# miniDCU_main.net
KiCad netlist of a schematic drawn in EAGLE
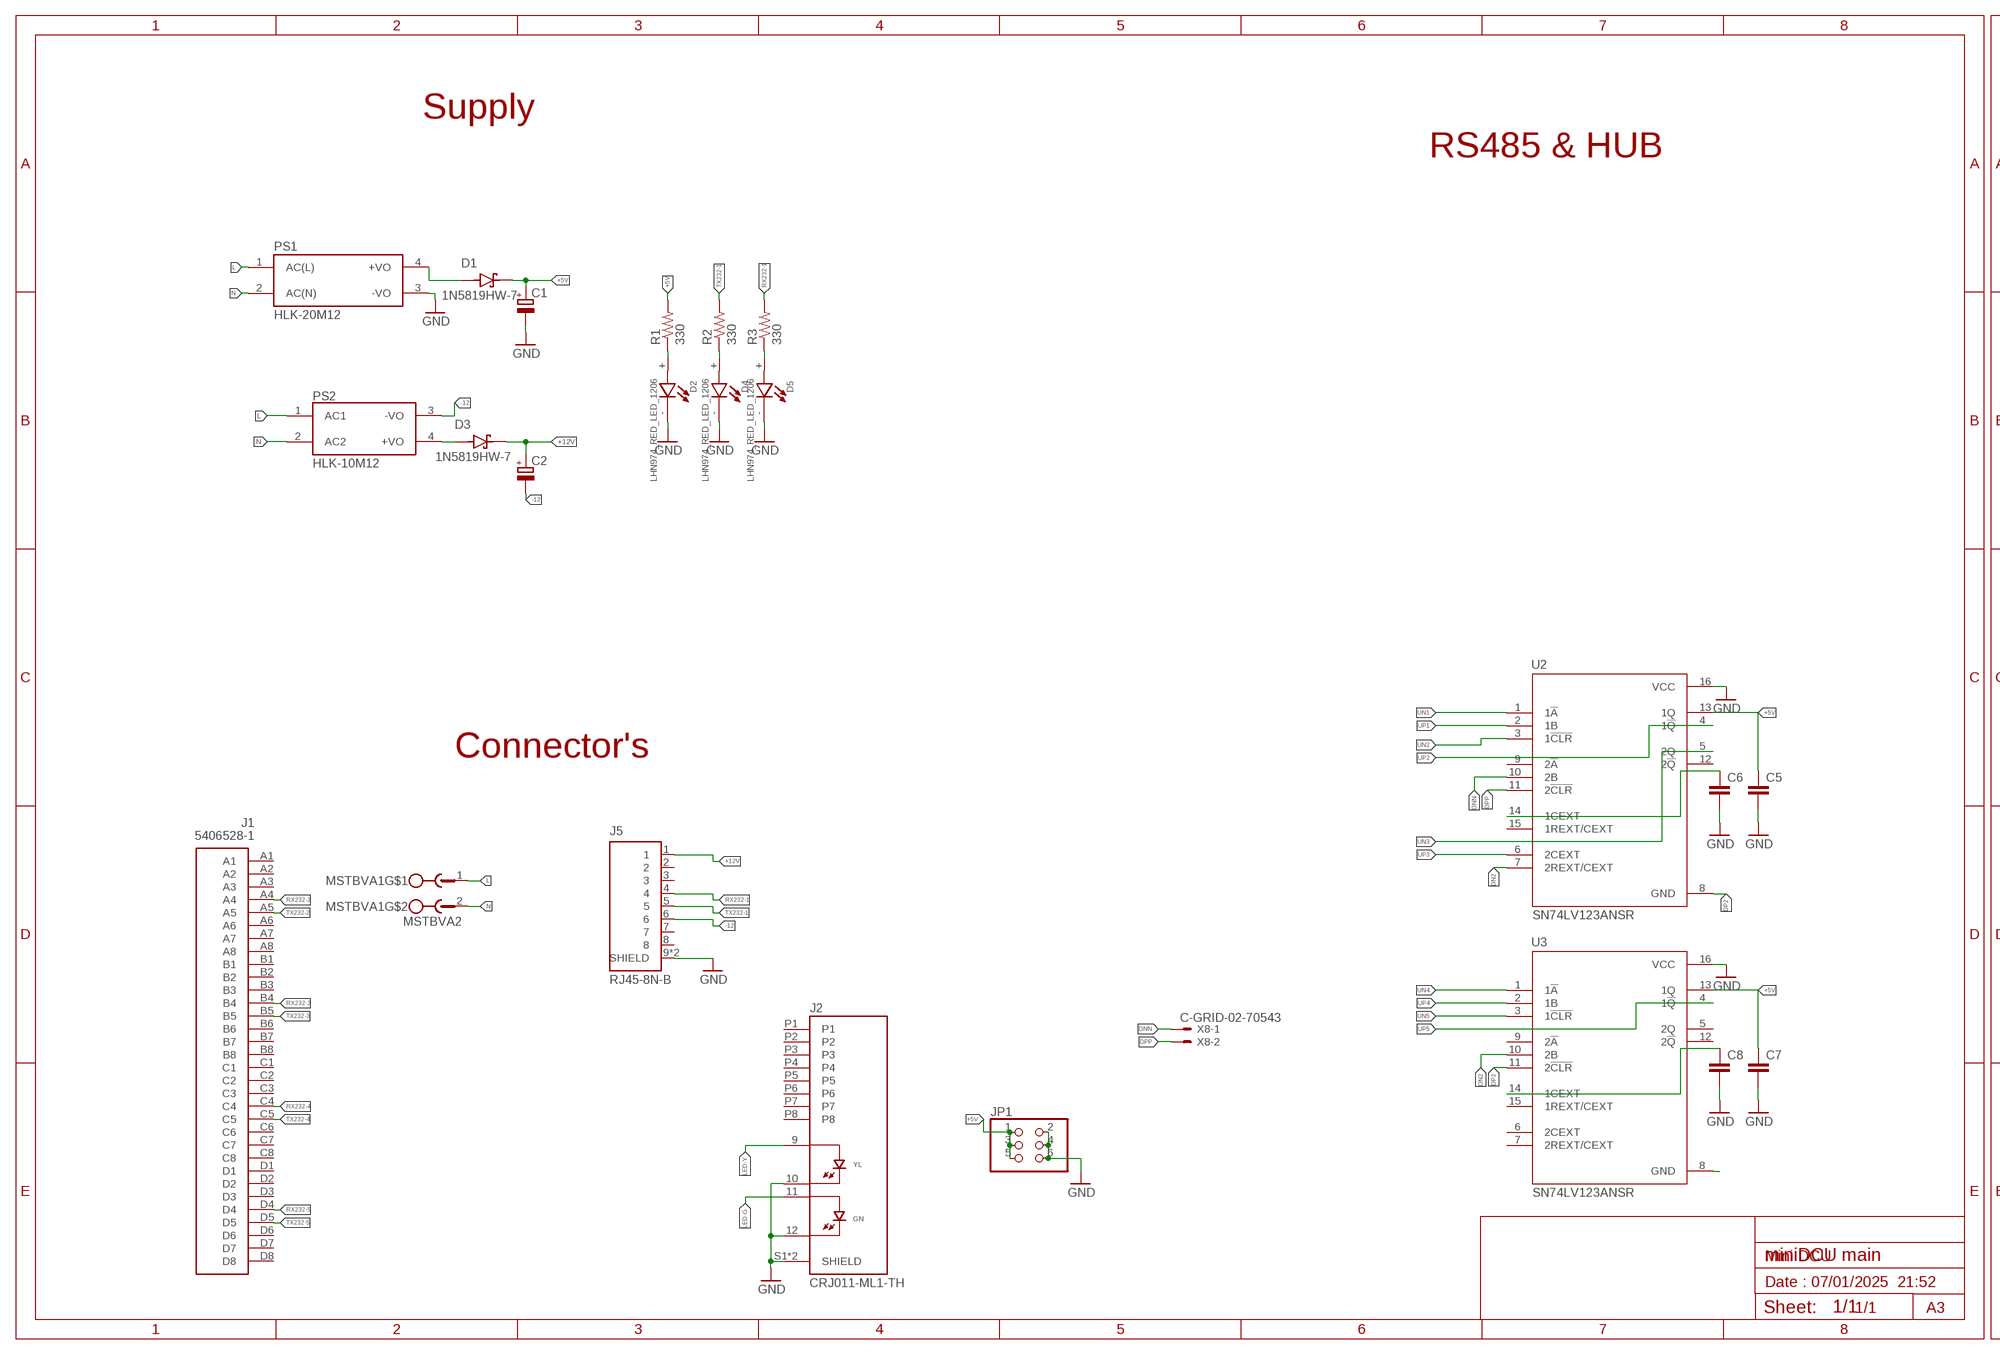
[diagram p0: schematic, sheet 1, part 1 of 2]
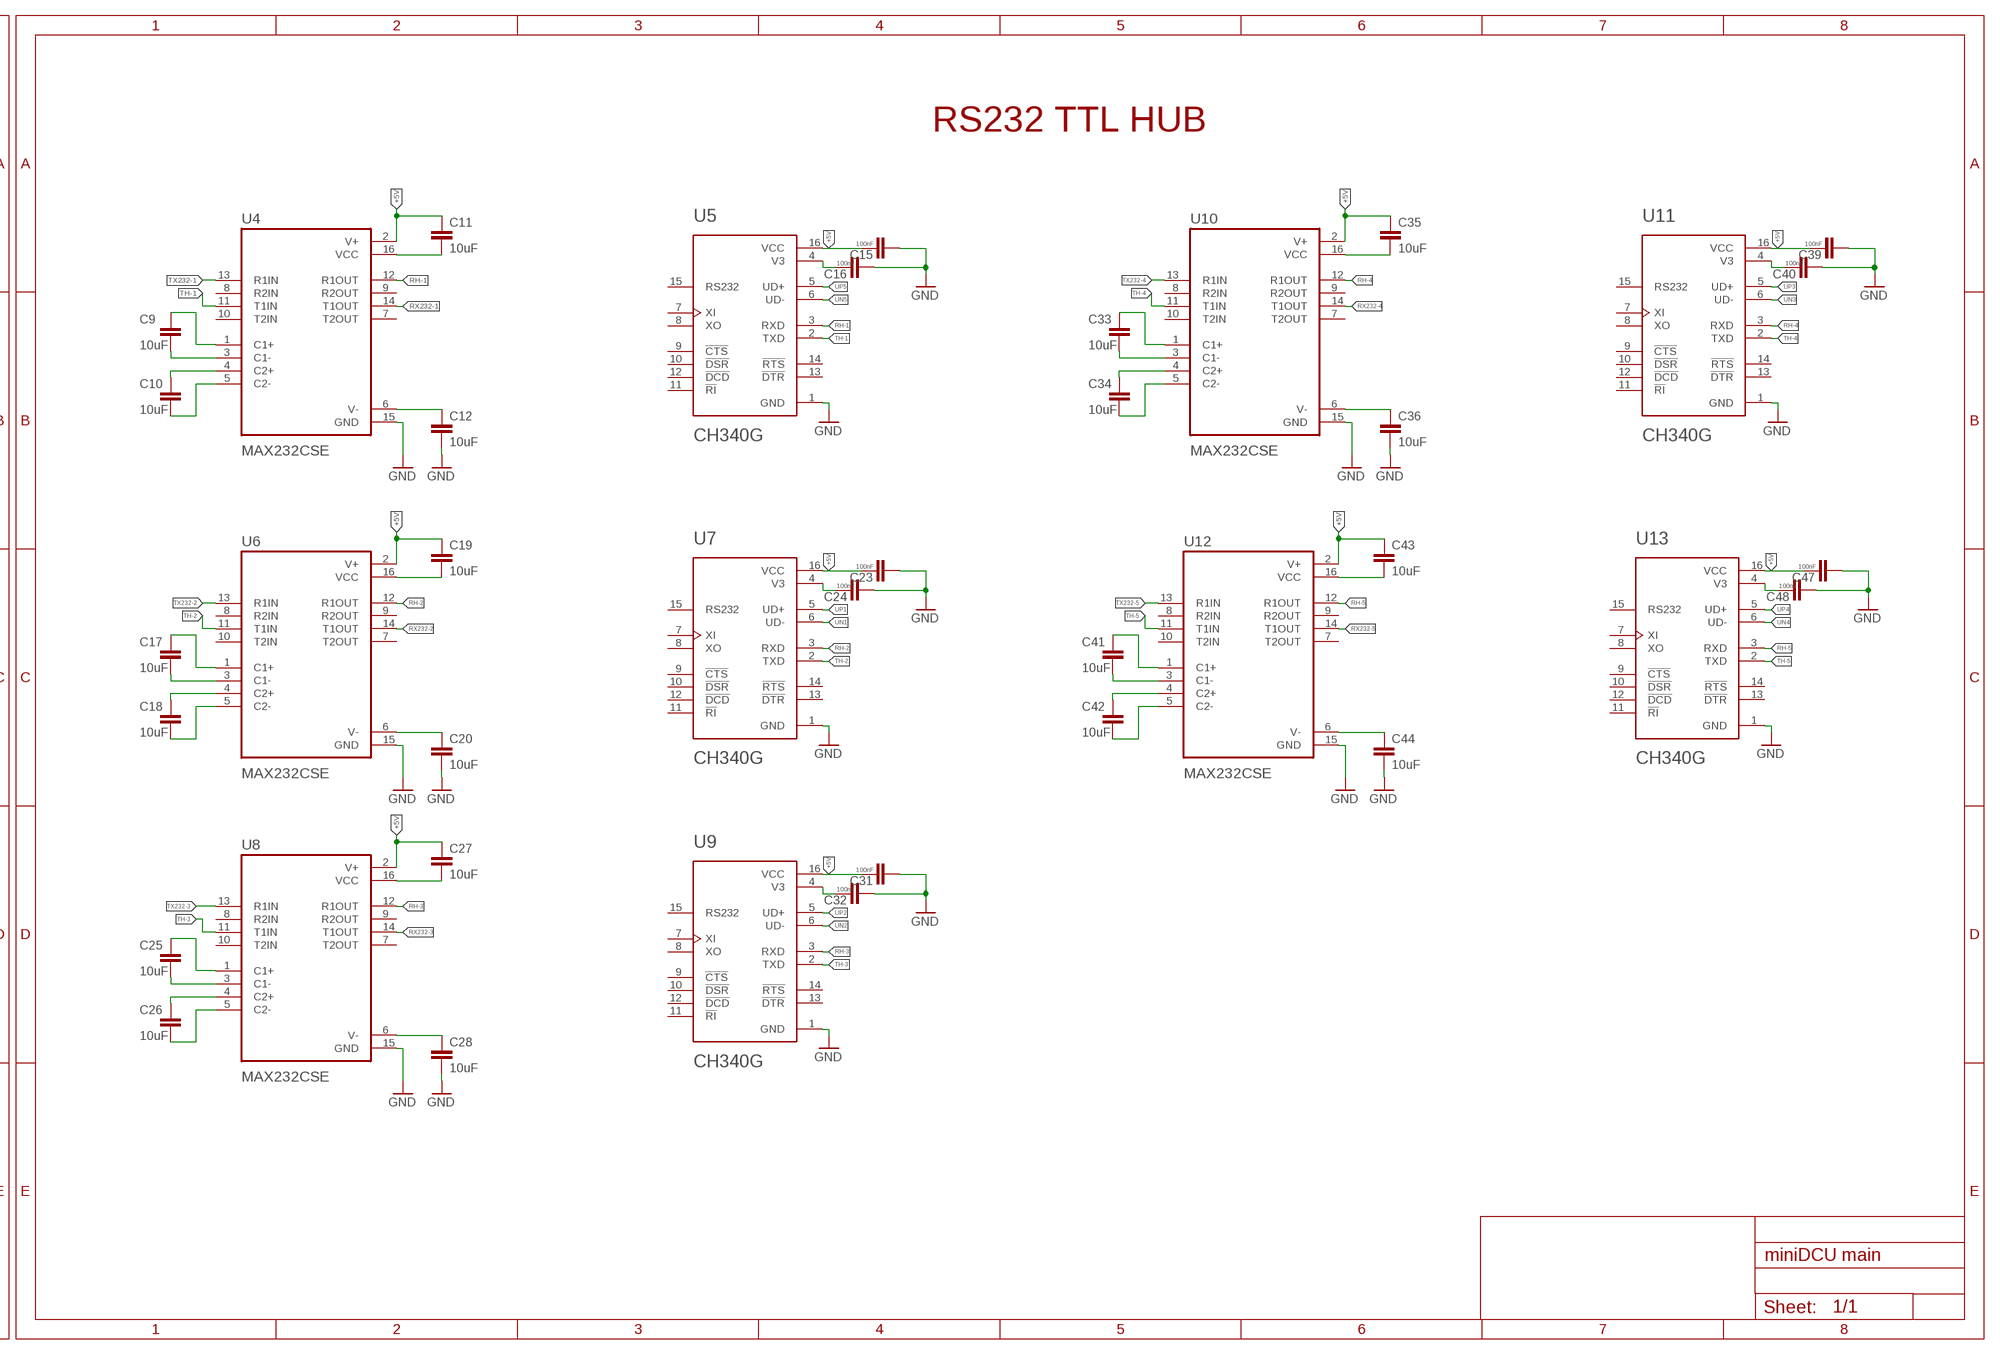
[diagram p1: schematic, sheet 1, part 2 of 2]

(export (version "E")
  (design (tool "Eeschema 10.0.6"))
  (components
    (comp (ref "C1")
      (value "CPOL-EU153CLV-0505")
      (footprint "eagle-import:153CLV-0505")
      (libsource (lib "eagle-import") (part "CPOL-EU153CLV-0505"))
    )
    (comp (ref "C2")
      (value "CPOL-EU153CLV-0505")
      (footprint "eagle-import:153CLV-0505")
      (libsource (lib "eagle-import") (part "CPOL-EU153CLV-0505"))
    )
    (comp (ref "C5")
      (value "C-EUC0603K")
      (footprint "eagle-import:C0603K")
      (libsource (lib "eagle-import") (part "C-EUC0603K"))
    )
    (comp (ref "C6")
      (value "C-EUC0603K")
      (footprint "eagle-import:C0603K")
      (libsource (lib "eagle-import") (part "C-EUC0603K"))
    )
    (comp (ref "C7")
      (value "C-EUC0603K")
      (footprint "eagle-import:C0603K")
      (libsource (lib "eagle-import") (part "C-EUC0603K"))
    )
    (comp (ref "C8")
      (value "C-EUC0603K")
      (footprint "eagle-import:C0603K")
      (libsource (lib "eagle-import") (part "C-EUC0603K"))
    )
    (comp (ref "C9")
      (value "10uF")
      (footprint "eagle-import:C0805")
      (libsource (lib "eagle-import") (part "C-EUC0805"))
    )
    (comp (ref "C10")
      (value "10uF")
      (footprint "eagle-import:C0805")
      (libsource (lib "eagle-import") (part "C-EUC0805"))
    )
    (comp (ref "C11")
      (value "10uF")
      (footprint "eagle-import:C0805")
      (libsource (lib "eagle-import") (part "C-EUC0805"))
    )
    (comp (ref "C12")
      (value "10uF")
      (footprint "eagle-import:C0805")
      (libsource (lib "eagle-import") (part "C-EUC0805"))
    )
    (comp (ref "C15")
      (value "100nF")
      (footprint "eagle-import:C0805K")
      (libsource (lib "eagle-import") (part "C-EUC0805K"))
    )
    (comp (ref "C16")
      (value "100nF")
      (footprint "eagle-import:C0805K")
      (libsource (lib "eagle-import") (part "C-EUC0805K"))
    )
    (comp (ref "C17")
      (value "10uF")
      (footprint "eagle-import:C0805")
      (libsource (lib "eagle-import") (part "C-EUC0805"))
    )
    (comp (ref "C18")
      (value "10uF")
      (footprint "eagle-import:C0805")
      (libsource (lib "eagle-import") (part "C-EUC0805"))
    )
    (comp (ref "C19")
      (value "10uF")
      (footprint "eagle-import:C0805")
      (libsource (lib "eagle-import") (part "C-EUC0805"))
    )
    (comp (ref "C20")
      (value "10uF")
      (footprint "eagle-import:C0805")
      (libsource (lib "eagle-import") (part "C-EUC0805"))
    )
    (comp (ref "C23")
      (value "100nF")
      (footprint "eagle-import:C0805K")
      (libsource (lib "eagle-import") (part "C-EUC0805K"))
    )
    (comp (ref "C24")
      (value "100nF")
      (footprint "eagle-import:C0805K")
      (libsource (lib "eagle-import") (part "C-EUC0805K"))
    )
    (comp (ref "C25")
      (value "10uF")
      (footprint "eagle-import:C0805")
      (libsource (lib "eagle-import") (part "C-EUC0805"))
    )
    (comp (ref "C26")
      (value "10uF")
      (footprint "eagle-import:C0805")
      (libsource (lib "eagle-import") (part "C-EUC0805"))
    )
    (comp (ref "C27")
      (value "10uF")
      (footprint "eagle-import:C0805")
      (libsource (lib "eagle-import") (part "C-EUC0805"))
    )
    (comp (ref "C28")
      (value "10uF")
      (footprint "eagle-import:C0805")
      (libsource (lib "eagle-import") (part "C-EUC0805"))
    )
    (comp (ref "C31")
      (value "100nF")
      (footprint "eagle-import:C0805K")
      (libsource (lib "eagle-import") (part "C-EUC0805K"))
    )
    (comp (ref "C32")
      (value "100nF")
      (footprint "eagle-import:C0805K")
      (libsource (lib "eagle-import") (part "C-EUC0805K"))
    )
    (comp (ref "C33")
      (value "10uF")
      (footprint "eagle-import:C0805")
      (libsource (lib "eagle-import") (part "C-EUC0805"))
    )
    (comp (ref "C34")
      (value "10uF")
      (footprint "eagle-import:C0805")
      (libsource (lib "eagle-import") (part "C-EUC0805"))
    )
    (comp (ref "C35")
      (value "10uF")
      (footprint "eagle-import:C0805")
      (libsource (lib "eagle-import") (part "C-EUC0805"))
    )
    (comp (ref "C36")
      (value "10uF")
      (footprint "eagle-import:C0805")
      (libsource (lib "eagle-import") (part "C-EUC0805"))
    )
    (comp (ref "C39")
      (value "100nF")
      (footprint "eagle-import:C0805K")
      (libsource (lib "eagle-import") (part "C-EUC0805K"))
    )
    (comp (ref "C40")
      (value "100nF")
      (footprint "eagle-import:C0805K")
      (libsource (lib "eagle-import") (part "C-EUC0805K"))
    )
    (comp (ref "C41")
      (value "10uF")
      (footprint "eagle-import:C0805")
      (libsource (lib "eagle-import") (part "C-EUC0805"))
    )
    (comp (ref "C42")
      (value "10uF")
      (footprint "eagle-import:C0805")
      (libsource (lib "eagle-import") (part "C-EUC0805"))
    )
    (comp (ref "C43")
      (value "10uF")
      (footprint "eagle-import:C0805")
      (libsource (lib "eagle-import") (part "C-EUC0805"))
    )
    (comp (ref "C44")
      (value "10uF")
      (footprint "eagle-import:C0805")
      (libsource (lib "eagle-import") (part "C-EUC0805"))
    )
    (comp (ref "C47")
      (value "100nF")
      (footprint "eagle-import:C0805K")
      (libsource (lib "eagle-import") (part "C-EUC0805K"))
    )
    (comp (ref "C48")
      (value "100nF")
      (footprint "eagle-import:C0805K")
      (libsource (lib "eagle-import") (part "C-EUC0805K"))
    )
    (comp (ref "D1")
      (value "1N5819HW-7")
      (footprint "eagle-import:SOD3715X145N")
      (fields (field (name "MF") "Diodes Inc."))
      (libsource (lib "eagle-import") (part "1N5819HW-7"))
    )
    (comp (ref "D2")
      (value "LHN974_RED_LED_1206")
      (footprint "eagle-import:LEDC3216X120N")
      (fields (field (name "MF") "Osram") (field (name "MP") "LHN974 RED LED 1206"))
      (libsource (lib "eagle-import") (part "LHN974_RED_LED_1206"))
    )
    (comp (ref "D3")
      (value "1N5819HW-7")
      (footprint "eagle-import:SOD3715X145N")
      (fields (field (name "MF") "Diodes Inc."))
      (libsource (lib "eagle-import") (part "1N5819HW-7"))
    )
    (comp (ref "D4")
      (value "LHN974_RED_LED_1206")
      (footprint "eagle-import:LEDC3216X120N")
      (fields (field (name "MF") "Osram") (field (name "MP") "LHN974 RED LED 1206"))
      (libsource (lib "eagle-import") (part "LHN974_RED_LED_1206"))
    )
    (comp (ref "D5")
      (value "LHN974_RED_LED_1206")
      (footprint "eagle-import:LEDC3216X120N")
      (fields (field (name "MF") "Osram") (field (name "MP") "LHN974 RED LED 1206"))
      (libsource (lib "eagle-import") (part "LHN974_RED_LED_1206"))
    )
    (comp (ref "J1")
      (value "5406528-1")
      (footprint "eagle-import:5406528-1")
      (fields (field (name "MF") "TE Connectivity"))
      (libsource (lib "eagle-import") (part "5406528-1"))
    )
    (comp (ref "J2")
      (value "CRJ011-ML1-TH")
      (footprint "eagle-import:CUI_CRJ011-ML1-TH")
      (fields (field (name "MF") "Same Sky"))
      (libsource (lib "eagle-import") (part "CRJ011-ML1-TH"))
    )
    (comp (ref "J5")
      (value "RJ45-8N-B")
      (footprint "eagle-import:TE_RJ45-8N-B")
      (fields (field (name "MF") "TE Connectivity"))
      (libsource (lib "eagle-import") (part "RJ45-8N-B"))
    )
    (comp (ref "JP1")
      (value "PINHD-2X3")
      (footprint "eagle-import:2X03")
      (libsource (lib "eagle-import") (part "PINHD-2X3"))
    )
    (comp (ref "MSTBVA1")
      (value "MSTBVA2")
      (footprint "eagle-import:MSTBVA2")
      (libsource (lib "eagle-import") (part "MSTBVA2"))
    )
    (comp (ref "PS1")
      (value "HLK-20M12")
      (footprint "eagle-import:CONV_HLK-20M12")
      (fields (field (name "MF") "Hi-link"))
      (libsource (lib "eagle-import") (part "HLK-20M12"))
    )
    (comp (ref "PS2")
      (value "HLK-10M12")
      (footprint "eagle-import:CONV_HLK-10M12")
      (fields (field (name "MF") "Hi-link"))
      (libsource (lib "eagle-import") (part "HLK-10M12"))
    )
    (comp (ref "R1")
      (value "330")
      (footprint "eagle-import:M0805")
      (libsource (lib "eagle-import") (part "R-US_M0805"))
    )
    (comp (ref "R2")
      (value "330")
      (footprint "eagle-import:M0805")
      (libsource (lib "eagle-import") (part "R-US_M0805"))
    )
    (comp (ref "R3")
      (value "330")
      (footprint "eagle-import:M0805")
      (libsource (lib "eagle-import") (part "R-US_M0805"))
    )
    (comp (ref "U2")
      (value "SN74LV123ANSR")
      (footprint "eagle-import:SOIC127P780X200-16N")
      (fields (field (name "DIGIKEY_PART_NUMBER") "296-46201-2-ND") (field (name "MF") "Texas Instruments"))
      (libsource (lib "eagle-import") (part "SN74LV123ANSR"))
    )
    (comp (ref "U3")
      (value "SN74LV123ANSR")
      (footprint "eagle-import:SOIC127P780X200-16N")
      (fields (field (name "DIGIKEY_PART_NUMBER") "296-46201-2-ND") (field (name "MF") "Texas Instruments"))
      (libsource (lib "eagle-import") (part "SN74LV123ANSR"))
    )
    (comp (ref "U4")
      (value "MAX232CSE")
      (footprint "eagle-import:SOIC127P600X175-16N")
      (fields (field (name "MF") "Maxim Integrated"))
      (libsource (lib "eagle-import") (part "MAX232CSE"))
    )
    (comp (ref "U5")
      (value "CH340G")
      (footprint "eagle-import:SOIC127P600X180-16N")
      (fields (field (name "MF") "WCH") (field (name "MP") "Ch340G"))
      (libsource (lib "eagle-import") (part "CH340G"))
    )
    (comp (ref "U6")
      (value "MAX232CSE")
      (footprint "eagle-import:SOIC127P600X175-16N")
      (fields (field (name "MF") "Maxim Integrated"))
      (libsource (lib "eagle-import") (part "MAX232CSE"))
    )
    (comp (ref "U7")
      (value "CH340G")
      (footprint "eagle-import:SOIC127P600X180-16N")
      (fields (field (name "MF") "WCH") (field (name "MP") "Ch340G"))
      (libsource (lib "eagle-import") (part "CH340G"))
    )
    (comp (ref "U8")
      (value "MAX232CSE")
      (footprint "eagle-import:SOIC127P600X175-16N")
      (fields (field (name "MF") "Maxim Integrated"))
      (libsource (lib "eagle-import") (part "MAX232CSE"))
    )
    (comp (ref "U9")
      (value "CH340G")
      (footprint "eagle-import:SOIC127P600X180-16N")
      (fields (field (name "MF") "WCH") (field (name "MP") "Ch340G"))
      (libsource (lib "eagle-import") (part "CH340G"))
    )
    (comp (ref "U10")
      (value "MAX232CSE")
      (footprint "eagle-import:SOIC127P600X175-16N")
      (fields (field (name "MF") "Maxim Integrated"))
      (libsource (lib "eagle-import") (part "MAX232CSE"))
    )
    (comp (ref "U11")
      (value "CH340G")
      (footprint "eagle-import:SOIC127P600X180-16N")
      (fields (field (name "MF") "WCH") (field (name "MP") "Ch340G"))
      (libsource (lib "eagle-import") (part "CH340G"))
    )
    (comp (ref "U12")
      (value "MAX232CSE")
      (footprint "eagle-import:SOIC127P600X175-16N")
      (fields (field (name "MF") "Maxim Integrated"))
      (libsource (lib "eagle-import") (part "MAX232CSE"))
    )
    (comp (ref "U13")
      (value "CH340G")
      (footprint "eagle-import:SOIC127P600X180-16N")
      (fields (field (name "MF") "WCH") (field (name "MP") "Ch340G"))
      (libsource (lib "eagle-import") (part "CH340G"))
    )
    (comp (ref "X8")
      (value "C-GRID-02-70543")
      (footprint "eagle-import:70543-02")
      (fields (field (name "MF") "MOLEX"))
      (libsource (lib "eagle-import") (part "C-GRID-02-70543"))
    )
  )
  (nets
    (net (code "1") (name "+5V") (class "Default")
      (node (ref "C1") (pin "+") (pinfunction "+_+") (pintype "passive"))
      (node (ref "C11") (pin "1") (pinfunction "1_1") (pintype "passive"))
      (node (ref "C15") (pin "1") (pinfunction "1_1") (pintype "passive"))
      (node (ref "C19") (pin "1") (pinfunction "1_1") (pintype "passive"))
      (node (ref "C23") (pin "1") (pinfunction "1_1") (pintype "passive"))
      (node (ref "C27") (pin "1") (pinfunction "1_1") (pintype "passive"))
      (node (ref "C31") (pin "1") (pinfunction "1_1") (pintype "passive"))
      (node (ref "C35") (pin "1") (pinfunction "1_1") (pintype "passive"))
      (node (ref "C39") (pin "1") (pinfunction "1_1") (pintype "passive"))
      (node (ref "C43") (pin "1") (pinfunction "1_1") (pintype "passive"))
      (node (ref "C47") (pin "1") (pinfunction "1_1") (pintype "passive"))
      (node (ref "C5") (pin "1") (pinfunction "1_1") (pintype "passive"))
      (node (ref "C7") (pin "1") (pinfunction "1_1") (pintype "passive"))
      (node (ref "D1") (pin "C") (pinfunction "K_C") (pintype "passive"))
      (node (ref "JP1") (pin "1") (pinfunction "1_1") (pintype "passive"))
      (node (ref "JP1") (pin "3") (pinfunction "3_3") (pintype "passive"))
      (node (ref "JP1") (pin "5") (pinfunction "5_5") (pintype "passive"))
      (node (ref "R1") (pin "2") (pinfunction "2_2") (pintype "passive"))
      (node (ref "U10") (pin "2") (pinfunction "V+_2") (pintype "power_in"))
      (node (ref "U11") (pin "16") (pinfunction "VCC_16") (pintype "power_in"))
      (node (ref "U12") (pin "2") (pinfunction "V+_2") (pintype "power_in"))
      (node (ref "U13") (pin "16") (pinfunction "VCC_16") (pintype "power_in"))
      (node (ref "U2") (pin "13") (pinfunction "1Q_13") (pintype "output"))
      (node (ref "U3") (pin "13") (pinfunction "1Q_13") (pintype "output"))
      (node (ref "U4") (pin "2") (pinfunction "V+_2") (pintype "power_in"))
      (node (ref "U5") (pin "16") (pinfunction "VCC_16") (pintype "power_in"))
      (node (ref "U6") (pin "2") (pinfunction "V+_2") (pintype "power_in"))
      (node (ref "U7") (pin "16") (pinfunction "VCC_16") (pintype "power_in"))
      (node (ref "U8") (pin "2") (pinfunction "V+_2") (pintype "power_in"))
      (node (ref "U9") (pin "16") (pinfunction "VCC_16") (pintype "power_in"))
    )
    (net (code "2") (name "+12V") (class "Default")
      (node (ref "C2") (pin "+") (pinfunction "+_+") (pintype "passive"))
      (node (ref "D3") (pin "C") (pinfunction "K_C") (pintype "passive"))
      (node (ref "J5") (pin "1") (pinfunction "1_1") (pintype "passive"))
    )
    (net (code "3") (name "-12") (class "Default")
      (node (ref "C2") (pin "-") (pinfunction "-_-") (pintype "passive"))
      (node (ref "J5") (pin "6") (pinfunction "6_6") (pintype "passive"))
      (node (ref "PS2") (pin "3") (pinfunction "-VO_3") (pintype "output"))
    )
    (net (code "4") (name "DN2") (class "Default")
      (node (ref "U2") (pin "7") (pinfunction "2REXT/CEXT_7") (pintype "bidirectional"))
      (node (ref "U3") (pin "10") (pinfunction "2B_10") (pintype "input"))
    )
    (net (code "5") (name "DNN") (class "Default")
      (node (ref "U2") (pin "10") (pinfunction "2B_10") (pintype "input"))
      (node (ref "X8") (pin "1") (pinfunction "S_1") (pintype "passive"))
    )
    (net (code "6") (name "DP2") (class "Default")
      (node (ref "U2") (pin "8") (pinfunction "GND_8") (pintype "power_in"))
      (node (ref "U3") (pin "11") (pinfunction "2~{CLR}_11") (pintype "input"))
    )
    (net (code "7") (name "DPP") (class "Default")
      (node (ref "U2") (pin "11") (pinfunction "2~{CLR}_11") (pintype "input"))
      (node (ref "X8") (pin "2") (pinfunction "S_2") (pintype "passive"))
    )
    (net (code "8") (name "GND") (class "Default")
      (node (ref "C1") (pin "-") (pinfunction "-_-") (pintype "passive"))
      (node (ref "C12") (pin "2") (pinfunction "2_2") (pintype "passive"))
      (node (ref "C15") (pin "2") (pinfunction "2_2") (pintype "passive"))
      (node (ref "C16") (pin "2") (pinfunction "2_2") (pintype "passive"))
      (node (ref "C20") (pin "2") (pinfunction "2_2") (pintype "passive"))
      (node (ref "C23") (pin "2") (pinfunction "2_2") (pintype "passive"))
      (node (ref "C24") (pin "2") (pinfunction "2_2") (pintype "passive"))
      (node (ref "C28") (pin "2") (pinfunction "2_2") (pintype "passive"))
      (node (ref "C31") (pin "2") (pinfunction "2_2") (pintype "passive"))
      (node (ref "C32") (pin "2") (pinfunction "2_2") (pintype "passive"))
      (node (ref "C36") (pin "2") (pinfunction "2_2") (pintype "passive"))
      (node (ref "C39") (pin "2") (pinfunction "2_2") (pintype "passive"))
      (node (ref "C40") (pin "2") (pinfunction "2_2") (pintype "passive"))
      (node (ref "C44") (pin "2") (pinfunction "2_2") (pintype "passive"))
      (node (ref "C47") (pin "2") (pinfunction "2_2") (pintype "passive"))
      (node (ref "C48") (pin "2") (pinfunction "2_2") (pintype "passive"))
      (node (ref "C5") (pin "2") (pinfunction "2_2") (pintype "passive"))
      (node (ref "C6") (pin "2") (pinfunction "2_2") (pintype "passive"))
      (node (ref "C7") (pin "2") (pinfunction "2_2") (pintype "passive"))
      (node (ref "C8") (pin "2") (pinfunction "2_2") (pintype "passive"))
      (node (ref "D2") (pin "-") (pinfunction "-_-") (pintype "passive"))
      (node (ref "D4") (pin "-") (pinfunction "-_-") (pintype "passive"))
      (node (ref "D5") (pin "-") (pinfunction "-_-") (pintype "passive"))
      (node (ref "J2") (pin "10") (pinfunction "10_10") (pintype "passive"))
      (node (ref "J2") (pin "12") (pinfunction "12_12") (pintype "passive"))
      (node (ref "J2") (pin "S1") (pinfunction "SHIELD_S1") (pintype "passive"))
      (node (ref "J2") (pin "S2") (pinfunction "SHIELD_S2") (pintype "passive"))
      (node (ref "J5") (pin "10") (pinfunction "SHIELD_10") (pintype "passive"))
      (node (ref "J5") (pin "9") (pinfunction "SHIELD_9") (pintype "passive"))
      (node (ref "JP1") (pin "2") (pinfunction "2_2") (pintype "passive"))
      (node (ref "JP1") (pin "4") (pinfunction "4_4") (pintype "passive"))
      (node (ref "JP1") (pin "6") (pinfunction "6_6") (pintype "passive"))
      (node (ref "PS1") (pin "3") (pinfunction "-VO_3") (pintype "output"))
      (node (ref "U10") (pin "15") (pinfunction "GND_15") (pintype "power_in"))
      (node (ref "U11") (pin "1") (pinfunction "GND_1") (pintype "power_in"))
      (node (ref "U12") (pin "15") (pinfunction "GND_15") (pintype "power_in"))
      (node (ref "U13") (pin "1") (pinfunction "GND_1") (pintype "power_in"))
      (node (ref "U2") (pin "16") (pinfunction "VCC_16") (pintype "power_in"))
      (node (ref "U3") (pin "16") (pinfunction "VCC_16") (pintype "power_in"))
      (node (ref "U4") (pin "15") (pinfunction "GND_15") (pintype "power_in"))
      (node (ref "U5") (pin "1") (pinfunction "GND_1") (pintype "power_in"))
      (node (ref "U6") (pin "15") (pinfunction "GND_15") (pintype "power_in"))
      (node (ref "U7") (pin "1") (pinfunction "GND_1") (pintype "power_in"))
      (node (ref "U8") (pin "15") (pinfunction "GND_15") (pintype "power_in"))
      (node (ref "U9") (pin "1") (pinfunction "GND_1") (pintype "power_in"))
    )
    (net (code "9") (name "L") (class "Default")
      (node (ref "MSTBVA1") (pin "1") (pinfunction "1_1") (pintype "passive"))
      (node (ref "PS1") (pin "1") (pinfunction "AC(L)_1") (pintype "input"))
      (node (ref "PS2") (pin "1") (pinfunction "AC1_1") (pintype "input"))
    )
    (net (code "10") (name "LED-G") (class "Default")
      (node (ref "J2") (pin "11") (pinfunction "11_11") (pintype "passive"))
    )
    (net (code "11") (name "LED-Y") (class "Default")
      (node (ref "J2") (pin "9") (pinfunction "9_9") (pintype "passive"))
    )
    (net (code "12") (name "N") (class "Default")
      (node (ref "MSTBVA1") (pin "2") (pinfunction "1_2") (pintype "passive"))
      (node (ref "PS1") (pin "2") (pinfunction "AC(N)_2") (pintype "input"))
      (node (ref "PS2") (pin "2") (pinfunction "AC2_2") (pintype "input"))
    )
    (net (code "13") (name "Net-(D2-Pad+)") (class "Default")
      (node (ref "D2") (pin "+") (pinfunction "+_+") (pintype "passive"))
      (node (ref "R1") (pin "1") (pinfunction "1_1") (pintype "passive"))
    )
    (net (code "14") (name "Net-(D4-Pad+)") (class "Default")
      (node (ref "D4") (pin "+") (pinfunction "+_+") (pintype "passive"))
      (node (ref "R2") (pin "1") (pinfunction "1_1") (pintype "passive"))
    )
    (net (code "15") (name "Net-(D5-Pad+)") (class "Default")
      (node (ref "D5") (pin "+") (pinfunction "+_+") (pintype "passive"))
      (node (ref "R3") (pin "1") (pinfunction "1_1") (pintype "passive"))
    )
    (net (code "16") (name "Net-(PS1-+VO)") (class "Default")
      (node (ref "D1") (pin "A") (pinfunction "A_A") (pintype "passive"))
      (node (ref "PS1") (pin "4") (pinfunction "+VO_4") (pintype "output"))
    )
    (net (code "17") (name "Net-(PS2-+VO)") (class "Default")
      (node (ref "D3") (pin "A") (pinfunction "A_A") (pintype "passive"))
      (node (ref "PS2") (pin "4") (pinfunction "+VO_4") (pintype "output"))
    )
    (net (code "18") (name "Net-(U2-1CEXT)") (class "Default")
      (node (ref "C6") (pin "1") (pinfunction "1_1") (pintype "passive"))
      (node (ref "U2") (pin "14") (pinfunction "1CEXT_14") (pintype "bidirectional"))
    )
    (net (code "19") (name "Net-(U3-1CEXT)") (class "Default")
      (node (ref "C8") (pin "1") (pinfunction "1_1") (pintype "passive"))
      (node (ref "U3") (pin "14") (pinfunction "1CEXT_14") (pintype "bidirectional"))
    )
    (net (code "20") (name "Net-(U4-C1+)") (class "Default")
      (node (ref "C9") (pin "1") (pinfunction "1_1") (pintype "passive"))
      (node (ref "U4") (pin "1") (pinfunction "C1+_1") (pintype "bidirectional"))
    )
    (net (code "21") (name "Net-(U4-C1-)") (class "Default")
      (node (ref "C9") (pin "2") (pinfunction "2_2") (pintype "passive"))
      (node (ref "U4") (pin "3") (pinfunction "C1-_3") (pintype "bidirectional"))
    )
    (net (code "22") (name "Net-(U4-C2+)") (class "Default")
      (node (ref "C10") (pin "1") (pinfunction "1_1") (pintype "passive"))
      (node (ref "U4") (pin "4") (pinfunction "C2+_4") (pintype "bidirectional"))
    )
    (net (code "23") (name "Net-(U4-C2-)") (class "Default")
      (node (ref "C10") (pin "2") (pinfunction "2_2") (pintype "passive"))
      (node (ref "U4") (pin "5") (pinfunction "C2-_5") (pintype "bidirectional"))
    )
    (net (code "24") (name "Net-(U4-V-)") (class "Default")
      (node (ref "C12") (pin "1") (pinfunction "1_1") (pintype "passive"))
      (node (ref "U4") (pin "6") (pinfunction "V-_6") (pintype "power_in"))
    )
    (net (code "25") (name "Net-(U4-VCC)") (class "Default")
      (node (ref "C11") (pin "2") (pinfunction "2_2") (pintype "passive"))
      (node (ref "U4") (pin "16") (pinfunction "VCC_16") (pintype "power_in"))
    )
    (net (code "26") (name "Net-(U5-V3)") (class "Default")
      (node (ref "C16") (pin "1") (pinfunction "1_1") (pintype "passive"))
      (node (ref "U5") (pin "4") (pinfunction "V3_4") (pintype "power_in"))
    )
    (net (code "27") (name "Net-(U6-C1+)") (class "Default")
      (node (ref "C17") (pin "1") (pinfunction "1_1") (pintype "passive"))
      (node (ref "U6") (pin "1") (pinfunction "C1+_1") (pintype "bidirectional"))
    )
    (net (code "28") (name "Net-(U6-C1-)") (class "Default")
      (node (ref "C17") (pin "2") (pinfunction "2_2") (pintype "passive"))
      (node (ref "U6") (pin "3") (pinfunction "C1-_3") (pintype "bidirectional"))
    )
    (net (code "29") (name "Net-(U6-C2+)") (class "Default")
      (node (ref "C18") (pin "1") (pinfunction "1_1") (pintype "passive"))
      (node (ref "U6") (pin "4") (pinfunction "C2+_4") (pintype "bidirectional"))
    )
    (net (code "30") (name "Net-(U6-C2-)") (class "Default")
      (node (ref "C18") (pin "2") (pinfunction "2_2") (pintype "passive"))
      (node (ref "U6") (pin "5") (pinfunction "C2-_5") (pintype "bidirectional"))
    )
    (net (code "31") (name "Net-(U6-V-)") (class "Default")
      (node (ref "C20") (pin "1") (pinfunction "1_1") (pintype "passive"))
      (node (ref "U6") (pin "6") (pinfunction "V-_6") (pintype "power_in"))
    )
    (net (code "32") (name "Net-(U6-VCC)") (class "Default")
      (node (ref "C19") (pin "2") (pinfunction "2_2") (pintype "passive"))
      (node (ref "U6") (pin "16") (pinfunction "VCC_16") (pintype "power_in"))
    )
    (net (code "33") (name "Net-(U7-V3)") (class "Default")
      (node (ref "C24") (pin "1") (pinfunction "1_1") (pintype "passive"))
      (node (ref "U7") (pin "4") (pinfunction "V3_4") (pintype "power_in"))
    )
    (net (code "34") (name "Net-(U8-C1+)") (class "Default")
      (node (ref "C25") (pin "1") (pinfunction "1_1") (pintype "passive"))
      (node (ref "U8") (pin "1") (pinfunction "C1+_1") (pintype "bidirectional"))
    )
    (net (code "35") (name "Net-(U8-C1-)") (class "Default")
      (node (ref "C25") (pin "2") (pinfunction "2_2") (pintype "passive"))
      (node (ref "U8") (pin "3") (pinfunction "C1-_3") (pintype "bidirectional"))
    )
    (net (code "36") (name "Net-(U8-C2+)") (class "Default")
      (node (ref "C26") (pin "1") (pinfunction "1_1") (pintype "passive"))
      (node (ref "U8") (pin "4") (pinfunction "C2+_4") (pintype "bidirectional"))
    )
    (net (code "37") (name "Net-(U8-C2-)") (class "Default")
      (node (ref "C26") (pin "2") (pinfunction "2_2") (pintype "passive"))
      (node (ref "U8") (pin "5") (pinfunction "C2-_5") (pintype "bidirectional"))
    )
    (net (code "38") (name "Net-(U8-V-)") (class "Default")
      (node (ref "C28") (pin "1") (pinfunction "1_1") (pintype "passive"))
      (node (ref "U8") (pin "6") (pinfunction "V-_6") (pintype "power_in"))
    )
    (net (code "39") (name "Net-(U8-VCC)") (class "Default")
      (node (ref "C27") (pin "2") (pinfunction "2_2") (pintype "passive"))
      (node (ref "U8") (pin "16") (pinfunction "VCC_16") (pintype "power_in"))
    )
    (net (code "40") (name "Net-(U9-V3)") (class "Default")
      (node (ref "C32") (pin "1") (pinfunction "1_1") (pintype "passive"))
      (node (ref "U9") (pin "4") (pinfunction "V3_4") (pintype "power_in"))
    )
    (net (code "41") (name "Net-(U10-C1+)") (class "Default")
      (node (ref "C33") (pin "1") (pinfunction "1_1") (pintype "passive"))
      (node (ref "U10") (pin "1") (pinfunction "C1+_1") (pintype "bidirectional"))
    )
    (net (code "42") (name "Net-(U10-C1-)") (class "Default")
      (node (ref "C33") (pin "2") (pinfunction "2_2") (pintype "passive"))
      (node (ref "U10") (pin "3") (pinfunction "C1-_3") (pintype "bidirectional"))
    )
    (net (code "43") (name "Net-(U10-C2+)") (class "Default")
      (node (ref "C34") (pin "1") (pinfunction "1_1") (pintype "passive"))
      (node (ref "U10") (pin "4") (pinfunction "C2+_4") (pintype "bidirectional"))
    )
    (net (code "44") (name "Net-(U10-C2-)") (class "Default")
      (node (ref "C34") (pin "2") (pinfunction "2_2") (pintype "passive"))
      (node (ref "U10") (pin "5") (pinfunction "C2-_5") (pintype "bidirectional"))
    )
    (net (code "45") (name "Net-(U10-V-)") (class "Default")
      (node (ref "C36") (pin "1") (pinfunction "1_1") (pintype "passive"))
      (node (ref "U10") (pin "6") (pinfunction "V-_6") (pintype "power_in"))
    )
    (net (code "46") (name "Net-(U10-VCC)") (class "Default")
      (node (ref "C35") (pin "2") (pinfunction "2_2") (pintype "passive"))
      (node (ref "U10") (pin "16") (pinfunction "VCC_16") (pintype "power_in"))
    )
    (net (code "47") (name "Net-(U11-V3)") (class "Default")
      (node (ref "C40") (pin "1") (pinfunction "1_1") (pintype "passive"))
      (node (ref "U11") (pin "4") (pinfunction "V3_4") (pintype "power_in"))
    )
    (net (code "48") (name "Net-(U12-C1+)") (class "Default")
      (node (ref "C41") (pin "1") (pinfunction "1_1") (pintype "passive"))
      (node (ref "U12") (pin "1") (pinfunction "C1+_1") (pintype "bidirectional"))
    )
    (net (code "49") (name "Net-(U12-C1-)") (class "Default")
      (node (ref "C41") (pin "2") (pinfunction "2_2") (pintype "passive"))
      (node (ref "U12") (pin "3") (pinfunction "C1-_3") (pintype "bidirectional"))
    )
    (net (code "50") (name "Net-(U12-C2+)") (class "Default")
      (node (ref "C42") (pin "1") (pinfunction "1_1") (pintype "passive"))
      (node (ref "U12") (pin "4") (pinfunction "C2+_4") (pintype "bidirectional"))
    )
    (net (code "51") (name "Net-(U12-C2-)") (class "Default")
      (node (ref "C42") (pin "2") (pinfunction "2_2") (pintype "passive"))
      (node (ref "U12") (pin "5") (pinfunction "C2-_5") (pintype "bidirectional"))
    )
    (net (code "52") (name "Net-(U12-V-)") (class "Default")
      (node (ref "C44") (pin "1") (pinfunction "1_1") (pintype "passive"))
      (node (ref "U12") (pin "6") (pinfunction "V-_6") (pintype "power_in"))
    )
    (net (code "53") (name "Net-(U12-VCC)") (class "Default")
      (node (ref "C43") (pin "2") (pinfunction "2_2") (pintype "passive"))
      (node (ref "U12") (pin "16") (pinfunction "VCC_16") (pintype "power_in"))
    )
    (net (code "54") (name "Net-(U13-V3)") (class "Default")
      (node (ref "C48") (pin "1") (pinfunction "1_1") (pintype "passive"))
      (node (ref "U13") (pin "4") (pinfunction "V3_4") (pintype "power_in"))
    )
    (net (code "55") (name "RH-1") (class "Default")
      (node (ref "U4") (pin "12") (pinfunction "R1OUT_12") (pintype "output"))
      (node (ref "U5") (pin "3") (pinfunction "RXD_3") (pintype "input"))
    )
    (net (code "56") (name "RH-2") (class "Default")
      (node (ref "U6") (pin "12") (pinfunction "R1OUT_12") (pintype "output"))
      (node (ref "U7") (pin "3") (pinfunction "RXD_3") (pintype "input"))
    )
    (net (code "57") (name "RH-3") (class "Default")
      (node (ref "U8") (pin "12") (pinfunction "R1OUT_12") (pintype "output"))
      (node (ref "U9") (pin "3") (pinfunction "RXD_3") (pintype "input"))
    )
    (net (code "58") (name "RH-4") (class "Default")
      (node (ref "U10") (pin "12") (pinfunction "R1OUT_12") (pintype "output"))
      (node (ref "U11") (pin "3") (pinfunction "RXD_3") (pintype "input"))
    )
    (net (code "59") (name "RH-5") (class "Default")
      (node (ref "U12") (pin "12") (pinfunction "R1OUT_12") (pintype "output"))
      (node (ref "U13") (pin "3") (pinfunction "RXD_3") (pintype "input"))
    )
    (net (code "60") (name "RX232-1") (class "Default")
      (node (ref "J5") (pin "4") (pinfunction "4_4") (pintype "passive"))
      (node (ref "R3") (pin "2") (pinfunction "2_2") (pintype "passive"))
      (node (ref "U4") (pin "14") (pinfunction "T1OUT_14") (pintype "output"))
    )
    (net (code "61") (name "RX232-2") (class "Default")
      (node (ref "J1") (pin "A4") (pinfunction "A4_A4") (pintype "bidirectional"))
      (node (ref "U6") (pin "14") (pinfunction "T1OUT_14") (pintype "output"))
    )
    (net (code "62") (name "RX232-3") (class "Default")
      (node (ref "J1") (pin "B4") (pinfunction "B4_B4") (pintype "bidirectional"))
      (node (ref "U8") (pin "14") (pinfunction "T1OUT_14") (pintype "output"))
    )
    (net (code "63") (name "RX232-4") (class "Default")
      (node (ref "J1") (pin "C4") (pinfunction "C4_C4") (pintype "bidirectional"))
      (node (ref "U10") (pin "14") (pinfunction "T1OUT_14") (pintype "output"))
    )
    (net (code "64") (name "RX232-5") (class "Default")
      (node (ref "J1") (pin "D4") (pinfunction "D4_D4") (pintype "bidirectional"))
      (node (ref "U12") (pin "14") (pinfunction "T1OUT_14") (pintype "output"))
    )
    (net (code "65") (name "TH-1") (class "Default")
      (node (ref "U4") (pin "11") (pinfunction "T1IN_11") (pintype "input"))
      (node (ref "U5") (pin "2") (pinfunction "TXD_2") (pintype "output"))
    )
    (net (code "66") (name "TH-2") (class "Default")
      (node (ref "U6") (pin "11") (pinfunction "T1IN_11") (pintype "input"))
      (node (ref "U7") (pin "2") (pinfunction "TXD_2") (pintype "output"))
    )
    (net (code "67") (name "TH-3") (class "Default")
      (node (ref "U8") (pin "11") (pinfunction "T1IN_11") (pintype "input"))
      (node (ref "U9") (pin "2") (pinfunction "TXD_2") (pintype "output"))
    )
    (net (code "68") (name "TH-4") (class "Default")
      (node (ref "U10") (pin "11") (pinfunction "T1IN_11") (pintype "input"))
      (node (ref "U11") (pin "2") (pinfunction "TXD_2") (pintype "output"))
    )
    (net (code "69") (name "TH-5") (class "Default")
      (node (ref "U12") (pin "11") (pinfunction "T1IN_11") (pintype "input"))
      (node (ref "U13") (pin "2") (pinfunction "TXD_2") (pintype "output"))
    )
    (net (code "70") (name "TX232-1") (class "Default")
      (node (ref "J5") (pin "5") (pinfunction "5_5") (pintype "passive"))
      (node (ref "R2") (pin "2") (pinfunction "2_2") (pintype "passive"))
      (node (ref "U4") (pin "13") (pinfunction "R1IN_13") (pintype "input"))
    )
    (net (code "71") (name "TX232-2") (class "Default")
      (node (ref "J1") (pin "A5") (pinfunction "A5_A5") (pintype "bidirectional"))
      (node (ref "U6") (pin "13") (pinfunction "R1IN_13") (pintype "input"))
    )
    (net (code "72") (name "TX232-3") (class "Default")
      (node (ref "J1") (pin "B5") (pinfunction "B5_B5") (pintype "bidirectional"))
      (node (ref "U8") (pin "13") (pinfunction "R1IN_13") (pintype "input"))
    )
    (net (code "73") (name "TX232-4") (class "Default")
      (node (ref "J1") (pin "C5") (pinfunction "C5_C5") (pintype "bidirectional"))
      (node (ref "U10") (pin "13") (pinfunction "R1IN_13") (pintype "input"))
    )
    (net (code "74") (name "TX232-5") (class "Default")
      (node (ref "J1") (pin "D5") (pinfunction "D5_D5") (pintype "bidirectional"))
      (node (ref "U12") (pin "13") (pinfunction "R1IN_13") (pintype "input"))
    )
    (net (code "75") (name "UN1") (class "Default")
      (node (ref "U2") (pin "1") (pinfunction "1~{A}_1") (pintype "input"))
      (node (ref "U7") (pin "6") (pinfunction "UD-_6") (pintype "bidirectional"))
    )
    (net (code "76") (name "UN2") (class "Default")
      (node (ref "U2") (pin "3") (pinfunction "1~{CLR}_3") (pintype "input"))
      (node (ref "U9") (pin "6") (pinfunction "UD-_6") (pintype "bidirectional"))
    )
    (net (code "77") (name "UN3") (class "Default")
      (node (ref "U11") (pin "6") (pinfunction "UD-_6") (pintype "bidirectional"))
      (node (ref "U2") (pin "5") (pinfunction "2Q_5") (pintype "output"))
    )
    (net (code "78") (name "UN4") (class "Default")
      (node (ref "U13") (pin "6") (pinfunction "UD-_6") (pintype "bidirectional"))
      (node (ref "U3") (pin "1") (pinfunction "1~{A}_1") (pintype "input"))
    )
    (net (code "79") (name "UN5") (class "Default")
      (node (ref "U3") (pin "3") (pinfunction "1~{CLR}_3") (pintype "input"))
      (node (ref "U5") (pin "6") (pinfunction "UD-_6") (pintype "bidirectional"))
    )
    (net (code "80") (name "UP1") (class "Default")
      (node (ref "U2") (pin "2") (pinfunction "1B_2") (pintype "input"))
      (node (ref "U7") (pin "5") (pinfunction "UD+_5") (pintype "bidirectional"))
    )
    (net (code "81") (name "UP2") (class "Default")
      (node (ref "U2") (pin "4") (pinfunction "1~{Q}_4") (pintype "output"))
      (node (ref "U9") (pin "5") (pinfunction "UD+_5") (pintype "bidirectional"))
    )
    (net (code "82") (name "UP3") (class "Default")
      (node (ref "U11") (pin "5") (pinfunction "UD+_5") (pintype "bidirectional"))
      (node (ref "U2") (pin "6") (pinfunction "2CEXT_6") (pintype "bidirectional"))
    )
    (net (code "83") (name "UP4") (class "Default")
      (node (ref "U13") (pin "5") (pinfunction "UD+_5") (pintype "bidirectional"))
      (node (ref "U3") (pin "2") (pinfunction "1B_2") (pintype "input"))
    )
    (net (code "84") (name "UP5") (class "Default")
      (node (ref "U3") (pin "4") (pinfunction "1~{Q}_4") (pintype "output"))
      (node (ref "U5") (pin "5") (pinfunction "UD+_5") (pintype "bidirectional"))
    )
    (net (code "85") (name "unconnected-(J1-PadA1)") (class "Default")
      (node (ref "J1") (pin "A1") (pinfunction "A1_A1") (pintype "bidirectional"))
    )
    (net (code "86") (name "unconnected-(J1-PadA2)") (class "Default")
      (node (ref "J1") (pin "A2") (pinfunction "A2_A2") (pintype "bidirectional"))
    )
    (net (code "87") (name "unconnected-(J1-PadA3)") (class "Default")
      (node (ref "J1") (pin "A3") (pinfunction "A3_A3") (pintype "bidirectional"))
    )
    (net (code "88") (name "unconnected-(J1-PadA6)") (class "Default")
      (node (ref "J1") (pin "A6") (pinfunction "A6_A6") (pintype "bidirectional"))
    )
    (net (code "89") (name "unconnected-(J1-PadA7)") (class "Default")
      (node (ref "J1") (pin "A7") (pinfunction "A7_A7") (pintype "bidirectional"))
    )
    (net (code "90") (name "unconnected-(J1-PadA8)") (class "Default")
      (node (ref "J1") (pin "A8") (pinfunction "A8_A8") (pintype "bidirectional"))
    )
    (net (code "91") (name "unconnected-(J1-PadB1)") (class "Default")
      (node (ref "J1") (pin "B1") (pinfunction "B1_B1") (pintype "bidirectional"))
    )
    (net (code "92") (name "unconnected-(J1-PadB2)") (class "Default")
      (node (ref "J1") (pin "B2") (pinfunction "B2_B2") (pintype "bidirectional"))
    )
    (net (code "93") (name "unconnected-(J1-PadB3)") (class "Default")
      (node (ref "J1") (pin "B3") (pinfunction "B3_B3") (pintype "bidirectional"))
    )
    (net (code "94") (name "unconnected-(J1-PadB6)") (class "Default")
      (node (ref "J1") (pin "B6") (pinfunction "B6_B6") (pintype "bidirectional"))
    )
    (net (code "95") (name "unconnected-(J1-PadB7)") (class "Default")
      (node (ref "J1") (pin "B7") (pinfunction "B7_B7") (pintype "bidirectional"))
    )
    (net (code "96") (name "unconnected-(J1-PadB8)") (class "Default")
      (node (ref "J1") (pin "B8") (pinfunction "B8_B8") (pintype "bidirectional"))
    )
    (net (code "97") (name "unconnected-(J1-PadC1)") (class "Default")
      (node (ref "J1") (pin "C1") (pinfunction "C1_C1") (pintype "bidirectional"))
    )
    (net (code "98") (name "unconnected-(J1-PadC2)") (class "Default")
      (node (ref "J1") (pin "C2") (pinfunction "C2_C2") (pintype "bidirectional"))
    )
    (net (code "99") (name "unconnected-(J1-PadC3)") (class "Default")
      (node (ref "J1") (pin "C3") (pinfunction "C3_C3") (pintype "bidirectional"))
    )
    (net (code "100") (name "unconnected-(J1-PadC6)") (class "Default")
      (node (ref "J1") (pin "C6") (pinfunction "C6_C6") (pintype "bidirectional"))
    )
    (net (code "101") (name "unconnected-(J1-PadC7)") (class "Default")
      (node (ref "J1") (pin "C7") (pinfunction "C7_C7") (pintype "bidirectional"))
    )
    (net (code "102") (name "unconnected-(J1-PadC8)") (class "Default")
      (node (ref "J1") (pin "C8") (pinfunction "C8_C8") (pintype "bidirectional"))
    )
    (net (code "103") (name "unconnected-(J1-PadD1)") (class "Default")
      (node (ref "J1") (pin "D1") (pinfunction "D1_D1") (pintype "bidirectional"))
    )
    (net (code "104") (name "unconnected-(J1-PadD2)") (class "Default")
      (node (ref "J1") (pin "D2") (pinfunction "D2_D2") (pintype "bidirectional"))
    )
    (net (code "105") (name "unconnected-(J1-PadD3)") (class "Default")
      (node (ref "J1") (pin "D3") (pinfunction "D3_D3") (pintype "bidirectional"))
    )
    (net (code "106") (name "unconnected-(J1-PadD6)") (class "Default")
      (node (ref "J1") (pin "D6") (pinfunction "D6_D6") (pintype "bidirectional"))
    )
    (net (code "107") (name "unconnected-(J1-PadD7)") (class "Default")
      (node (ref "J1") (pin "D7") (pinfunction "D7_D7") (pintype "bidirectional"))
    )
    (net (code "108") (name "unconnected-(J1-PadD8)") (class "Default")
      (node (ref "J1") (pin "D8") (pinfunction "D8_D8") (pintype "bidirectional"))
    )
    (net (code "109") (name "unconnected-(J2-PadP1)") (class "Default")
      (node (ref "J2") (pin "P1") (pinfunction "P1_P1") (pintype "passive"))
    )
    (net (code "110") (name "unconnected-(J2-PadP2)") (class "Default")
      (node (ref "J2") (pin "P2") (pinfunction "P2_P2") (pintype "passive"))
    )
    (net (code "111") (name "unconnected-(J2-PadP3)") (class "Default")
      (node (ref "J2") (pin "P3") (pinfunction "P3_P3") (pintype "passive"))
    )
    (net (code "112") (name "unconnected-(J2-PadP4)") (class "Default")
      (node (ref "J2") (pin "P4") (pinfunction "P4_P4") (pintype "passive"))
    )
    (net (code "113") (name "unconnected-(J2-PadP5)") (class "Default")
      (node (ref "J2") (pin "P5") (pinfunction "P5_P5") (pintype "passive"))
    )
    (net (code "114") (name "unconnected-(J2-PadP6)") (class "Default")
      (node (ref "J2") (pin "P6") (pinfunction "P6_P6") (pintype "passive"))
    )
    (net (code "115") (name "unconnected-(J2-PadP7)") (class "Default")
      (node (ref "J2") (pin "P7") (pinfunction "P7_P7") (pintype "passive"))
    )
    (net (code "116") (name "unconnected-(J2-PadP8)") (class "Default")
      (node (ref "J2") (pin "P8") (pinfunction "P8_P8") (pintype "passive"))
    )
    (net (code "117") (name "unconnected-(J5-Pad2)") (class "Default")
      (node (ref "J5") (pin "2") (pinfunction "2_2") (pintype "passive"))
    )
    (net (code "118") (name "unconnected-(J5-Pad3)") (class "Default")
      (node (ref "J5") (pin "3") (pinfunction "3_3") (pintype "passive"))
    )
    (net (code "119") (name "unconnected-(J5-Pad7)") (class "Default")
      (node (ref "J5") (pin "7") (pinfunction "7_7") (pintype "passive"))
    )
    (net (code "120") (name "unconnected-(J5-Pad8)") (class "Default")
      (node (ref "J5") (pin "8") (pinfunction "8_8") (pintype "passive"))
    )
    (net (code "121") (name "unconnected-(U2-1REXT{slash}CEXT-Pad15)") (class "Default")
      (node (ref "U2") (pin "15") (pinfunction "1REXT/CEXT_15") (pintype "bidirectional"))
    )
    (net (code "122") (name "unconnected-(U2-2~{A}-Pad9)") (class "Default")
      (node (ref "U2") (pin "9") (pinfunction "2~{A}_9") (pintype "input"))
    )
    (net (code "123") (name "unconnected-(U2-2~{Q}-Pad12)") (class "Default")
      (node (ref "U2") (pin "12") (pinfunction "2~{Q}_12") (pintype "output"))
    )
    (net (code "124") (name "unconnected-(U3-1REXT{slash}CEXT-Pad15)") (class "Default")
      (node (ref "U3") (pin "15") (pinfunction "1REXT/CEXT_15") (pintype "bidirectional"))
    )
    (net (code "125") (name "unconnected-(U3-2CEXT-Pad6)") (class "Default")
      (node (ref "U3") (pin "6") (pinfunction "2CEXT_6") (pintype "bidirectional"))
    )
    (net (code "126") (name "unconnected-(U3-2Q-Pad5)") (class "Default")
      (node (ref "U3") (pin "5") (pinfunction "2Q_5") (pintype "output"))
    )
    (net (code "127") (name "unconnected-(U3-2REXT{slash}CEXT-Pad7)") (class "Default")
      (node (ref "U3") (pin "7") (pinfunction "2REXT/CEXT_7") (pintype "bidirectional"))
    )
    (net (code "128") (name "unconnected-(U3-2~{A}-Pad9)") (class "Default")
      (node (ref "U3") (pin "9") (pinfunction "2~{A}_9") (pintype "input"))
    )
    (net (code "129") (name "unconnected-(U3-2~{Q}-Pad12)") (class "Default")
      (node (ref "U3") (pin "12") (pinfunction "2~{Q}_12") (pintype "output"))
    )
    (net (code "130") (name "unconnected-(U3-GND-Pad8)") (class "Default")
      (node (ref "U3") (pin "8") (pinfunction "GND_8") (pintype "power_in"))
    )
    (net (code "131") (name "unconnected-(U4-R2IN-Pad8)") (class "Default")
      (node (ref "U4") (pin "8") (pinfunction "R2IN_8") (pintype "input"))
    )
    (net (code "132") (name "unconnected-(U4-R2OUT-Pad9)") (class "Default")
      (node (ref "U4") (pin "9") (pinfunction "R2OUT_9") (pintype "output"))
    )
    (net (code "133") (name "unconnected-(U4-T2IN-Pad10)") (class "Default")
      (node (ref "U4") (pin "10") (pinfunction "T2IN_10") (pintype "input"))
    )
    (net (code "134") (name "unconnected-(U4-T2OUT-Pad7)") (class "Default")
      (node (ref "U4") (pin "7") (pinfunction "T2OUT_7") (pintype "output"))
    )
    (net (code "135") (name "unconnected-(U5-RS232-Pad15)") (class "Default")
      (node (ref "U5") (pin "15") (pinfunction "RS232_15") (pintype "input"))
    )
    (net (code "136") (name "unconnected-(U5-XI-Pad7)") (class "Default")
      (node (ref "U5") (pin "7") (pinfunction "XI_7") (pintype "input"))
    )
    (net (code "137") (name "unconnected-(U5-XO-Pad8)") (class "Default")
      (node (ref "U5") (pin "8") (pinfunction "XO_8") (pintype "output"))
    )
    (net (code "138") (name "unconnected-(U5-~{CTS}-Pad9)") (class "Default")
      (node (ref "U5") (pin "9") (pinfunction "~{CTS}_9") (pintype "input"))
    )
    (net (code "139") (name "unconnected-(U5-~{DCD}-Pad12)") (class "Default")
      (node (ref "U5") (pin "12") (pinfunction "~{DCD}_12") (pintype "input"))
    )
    (net (code "140") (name "unconnected-(U5-~{DSR}-Pad10)") (class "Default")
      (node (ref "U5") (pin "10") (pinfunction "~{DSR}_10") (pintype "input"))
    )
    (net (code "141") (name "unconnected-(U5-~{DTR}-Pad13)") (class "Default")
      (node (ref "U5") (pin "13") (pinfunction "~{DTR}_13") (pintype "output"))
    )
    (net (code "142") (name "unconnected-(U5-~{RI}-Pad11)") (class "Default")
      (node (ref "U5") (pin "11") (pinfunction "~{RI}_11") (pintype "input"))
    )
    (net (code "143") (name "unconnected-(U5-~{RTS}-Pad14)") (class "Default")
      (node (ref "U5") (pin "14") (pinfunction "~{RTS}_14") (pintype "output"))
    )
    (net (code "144") (name "unconnected-(U6-R2IN-Pad8)") (class "Default")
      (node (ref "U6") (pin "8") (pinfunction "R2IN_8") (pintype "input"))
    )
    (net (code "145") (name "unconnected-(U6-R2OUT-Pad9)") (class "Default")
      (node (ref "U6") (pin "9") (pinfunction "R2OUT_9") (pintype "output"))
    )
    (net (code "146") (name "unconnected-(U6-T2IN-Pad10)") (class "Default")
      (node (ref "U6") (pin "10") (pinfunction "T2IN_10") (pintype "input"))
    )
    (net (code "147") (name "unconnected-(U6-T2OUT-Pad7)") (class "Default")
      (node (ref "U6") (pin "7") (pinfunction "T2OUT_7") (pintype "output"))
    )
    (net (code "148") (name "unconnected-(U7-RS232-Pad15)") (class "Default")
      (node (ref "U7") (pin "15") (pinfunction "RS232_15") (pintype "input"))
    )
    (net (code "149") (name "unconnected-(U7-XI-Pad7)") (class "Default")
      (node (ref "U7") (pin "7") (pinfunction "XI_7") (pintype "input"))
    )
    (net (code "150") (name "unconnected-(U7-XO-Pad8)") (class "Default")
      (node (ref "U7") (pin "8") (pinfunction "XO_8") (pintype "output"))
    )
    (net (code "151") (name "unconnected-(U7-~{CTS}-Pad9)") (class "Default")
      (node (ref "U7") (pin "9") (pinfunction "~{CTS}_9") (pintype "input"))
    )
    (net (code "152") (name "unconnected-(U7-~{DCD}-Pad12)") (class "Default")
      (node (ref "U7") (pin "12") (pinfunction "~{DCD}_12") (pintype "input"))
    )
    (net (code "153") (name "unconnected-(U7-~{DSR}-Pad10)") (class "Default")
      (node (ref "U7") (pin "10") (pinfunction "~{DSR}_10") (pintype "input"))
    )
    (net (code "154") (name "unconnected-(U7-~{DTR}-Pad13)") (class "Default")
      (node (ref "U7") (pin "13") (pinfunction "~{DTR}_13") (pintype "output"))
    )
    (net (code "155") (name "unconnected-(U7-~{RI}-Pad11)") (class "Default")
      (node (ref "U7") (pin "11") (pinfunction "~{RI}_11") (pintype "input"))
    )
    (net (code "156") (name "unconnected-(U7-~{RTS}-Pad14)") (class "Default")
      (node (ref "U7") (pin "14") (pinfunction "~{RTS}_14") (pintype "output"))
    )
    (net (code "157") (name "unconnected-(U8-R2IN-Pad8)") (class "Default")
      (node (ref "U8") (pin "8") (pinfunction "R2IN_8") (pintype "input"))
    )
    (net (code "158") (name "unconnected-(U8-R2OUT-Pad9)") (class "Default")
      (node (ref "U8") (pin "9") (pinfunction "R2OUT_9") (pintype "output"))
    )
    (net (code "159") (name "unconnected-(U8-T2IN-Pad10)") (class "Default")
      (node (ref "U8") (pin "10") (pinfunction "T2IN_10") (pintype "input"))
    )
    (net (code "160") (name "unconnected-(U8-T2OUT-Pad7)") (class "Default")
      (node (ref "U8") (pin "7") (pinfunction "T2OUT_7") (pintype "output"))
    )
    (net (code "161") (name "unconnected-(U9-RS232-Pad15)") (class "Default")
      (node (ref "U9") (pin "15") (pinfunction "RS232_15") (pintype "input"))
    )
    (net (code "162") (name "unconnected-(U9-XI-Pad7)") (class "Default")
      (node (ref "U9") (pin "7") (pinfunction "XI_7") (pintype "input"))
    )
    (net (code "163") (name "unconnected-(U9-XO-Pad8)") (class "Default")
      (node (ref "U9") (pin "8") (pinfunction "XO_8") (pintype "output"))
    )
    (net (code "164") (name "unconnected-(U9-~{CTS}-Pad9)") (class "Default")
      (node (ref "U9") (pin "9") (pinfunction "~{CTS}_9") (pintype "input"))
    )
    (net (code "165") (name "unconnected-(U9-~{DCD}-Pad12)") (class "Default")
      (node (ref "U9") (pin "12") (pinfunction "~{DCD}_12") (pintype "input"))
    )
    (net (code "166") (name "unconnected-(U9-~{DSR}-Pad10)") (class "Default")
      (node (ref "U9") (pin "10") (pinfunction "~{DSR}_10") (pintype "input"))
    )
    (net (code "167") (name "unconnected-(U9-~{DTR}-Pad13)") (class "Default")
      (node (ref "U9") (pin "13") (pinfunction "~{DTR}_13") (pintype "output"))
    )
    (net (code "168") (name "unconnected-(U9-~{RI}-Pad11)") (class "Default")
      (node (ref "U9") (pin "11") (pinfunction "~{RI}_11") (pintype "input"))
    )
    (net (code "169") (name "unconnected-(U9-~{RTS}-Pad14)") (class "Default")
      (node (ref "U9") (pin "14") (pinfunction "~{RTS}_14") (pintype "output"))
    )
    (net (code "170") (name "unconnected-(U10-R2IN-Pad8)") (class "Default")
      (node (ref "U10") (pin "8") (pinfunction "R2IN_8") (pintype "input"))
    )
    (net (code "171") (name "unconnected-(U10-R2OUT-Pad9)") (class "Default")
      (node (ref "U10") (pin "9") (pinfunction "R2OUT_9") (pintype "output"))
    )
    (net (code "172") (name "unconnected-(U10-T2IN-Pad10)") (class "Default")
      (node (ref "U10") (pin "10") (pinfunction "T2IN_10") (pintype "input"))
    )
    (net (code "173") (name "unconnected-(U10-T2OUT-Pad7)") (class "Default")
      (node (ref "U10") (pin "7") (pinfunction "T2OUT_7") (pintype "output"))
    )
    (net (code "174") (name "unconnected-(U11-RS232-Pad15)") (class "Default")
      (node (ref "U11") (pin "15") (pinfunction "RS232_15") (pintype "input"))
    )
    (net (code "175") (name "unconnected-(U11-XI-Pad7)") (class "Default")
      (node (ref "U11") (pin "7") (pinfunction "XI_7") (pintype "input"))
    )
    (net (code "176") (name "unconnected-(U11-XO-Pad8)") (class "Default")
      (node (ref "U11") (pin "8") (pinfunction "XO_8") (pintype "output"))
    )
    (net (code "177") (name "unconnected-(U11-~{CTS}-Pad9)") (class "Default")
      (node (ref "U11") (pin "9") (pinfunction "~{CTS}_9") (pintype "input"))
    )
    (net (code "178") (name "unconnected-(U11-~{DCD}-Pad12)") (class "Default")
      (node (ref "U11") (pin "12") (pinfunction "~{DCD}_12") (pintype "input"))
    )
    (net (code "179") (name "unconnected-(U11-~{DSR}-Pad10)") (class "Default")
      (node (ref "U11") (pin "10") (pinfunction "~{DSR}_10") (pintype "input"))
    )
    (net (code "180") (name "unconnected-(U11-~{DTR}-Pad13)") (class "Default")
      (node (ref "U11") (pin "13") (pinfunction "~{DTR}_13") (pintype "output"))
    )
    (net (code "181") (name "unconnected-(U11-~{RI}-Pad11)") (class "Default")
      (node (ref "U11") (pin "11") (pinfunction "~{RI}_11") (pintype "input"))
    )
    (net (code "182") (name "unconnected-(U11-~{RTS}-Pad14)") (class "Default")
      (node (ref "U11") (pin "14") (pinfunction "~{RTS}_14") (pintype "output"))
    )
    (net (code "183") (name "unconnected-(U12-R2IN-Pad8)") (class "Default")
      (node (ref "U12") (pin "8") (pinfunction "R2IN_8") (pintype "input"))
    )
    (net (code "184") (name "unconnected-(U12-R2OUT-Pad9)") (class "Default")
      (node (ref "U12") (pin "9") (pinfunction "R2OUT_9") (pintype "output"))
    )
    (net (code "185") (name "unconnected-(U12-T2IN-Pad10)") (class "Default")
      (node (ref "U12") (pin "10") (pinfunction "T2IN_10") (pintype "input"))
    )
    (net (code "186") (name "unconnected-(U12-T2OUT-Pad7)") (class "Default")
      (node (ref "U12") (pin "7") (pinfunction "T2OUT_7") (pintype "output"))
    )
    (net (code "187") (name "unconnected-(U13-RS232-Pad15)") (class "Default")
      (node (ref "U13") (pin "15") (pinfunction "RS232_15") (pintype "input"))
    )
    (net (code "188") (name "unconnected-(U13-XI-Pad7)") (class "Default")
      (node (ref "U13") (pin "7") (pinfunction "XI_7") (pintype "input"))
    )
    (net (code "189") (name "unconnected-(U13-XO-Pad8)") (class "Default")
      (node (ref "U13") (pin "8") (pinfunction "XO_8") (pintype "output"))
    )
    (net (code "190") (name "unconnected-(U13-~{CTS}-Pad9)") (class "Default")
      (node (ref "U13") (pin "9") (pinfunction "~{CTS}_9") (pintype "input"))
    )
    (net (code "191") (name "unconnected-(U13-~{DCD}-Pad12)") (class "Default")
      (node (ref "U13") (pin "12") (pinfunction "~{DCD}_12") (pintype "input"))
    )
    (net (code "192") (name "unconnected-(U13-~{DSR}-Pad10)") (class "Default")
      (node (ref "U13") (pin "10") (pinfunction "~{DSR}_10") (pintype "input"))
    )
    (net (code "193") (name "unconnected-(U13-~{DTR}-Pad13)") (class "Default")
      (node (ref "U13") (pin "13") (pinfunction "~{DTR}_13") (pintype "output"))
    )
    (net (code "194") (name "unconnected-(U13-~{RI}-Pad11)") (class "Default")
      (node (ref "U13") (pin "11") (pinfunction "~{RI}_11") (pintype "input"))
    )
    (net (code "195") (name "unconnected-(U13-~{RTS}-Pad14)") (class "Default")
      (node (ref "U13") (pin "14") (pinfunction "~{RTS}_14") (pintype "output"))
    )
  )
)
